# CAN.net
KiCad netlist of a schematic drawn in Altium Designer
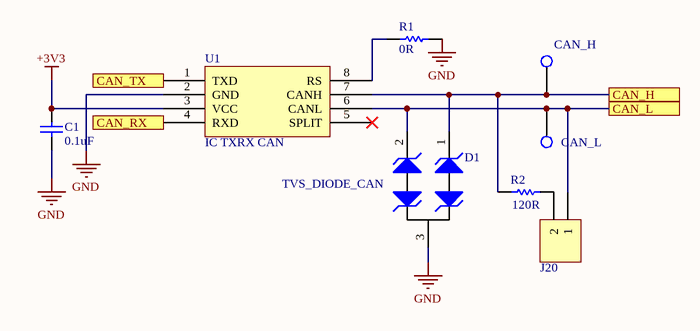
[diagram p0: CAN.SchDoc]

(export (version "E")
  (design (tool "Eeschema 10.0.6"))
  (components
    (comp (ref "C1")
      (value "0.1uF")
      (footprint "CAPC0603(1608)55_N")
      (description "CAP CER 0.1UF 16V X7R 0603")
      (fields (field (name "MANUFACTURER") "Yageo") (field (name "MPN") "CC0603KRX7R7BB104"))
      (libsource (lib "UWRT_Schematic_Library_2019") (part "CAP_0.1uF_16V_0603"))
    )
    (comp (ref "D1")
      (value "TVS_DIODE_CAN")
      (footprint "UWRT_Footprint_Library_2019:TVS_DIODE_CAN")
      (description "TVS DIODE 24V 41V SOT323-3")
      (fields (field (name "MANUFACTURER") "Nexperia USA Inc.") (field (name "MPN") "PESD2CAN,215"))
      (libsource (lib "UWRT_Schematic_Library_2019") (part "TVS_DIODE_CAN"))
    )
    (comp (ref "J20")
      (value "JUMPER_2")
      (footprint "HDR1X2")
      (description "HEADER 2X1")
      (libsource (lib "UWRT_Schematic_Library_2019") (part "JUMPER_2"))
    )
    (comp (ref "R1")
      (value "0R")
      (footprint "RESC0603(1608)_N")
      (description "RES SMD 0 OHM JUMPER 1/10W 0603")
      (fields (field (name "MANUFACTURER") "Yageo") (field (name "MPN") "RC0603JR-070RL"))
      (libsource (lib "UWRT_Schematic_Library_2019") (part "RES_0R_0603"))
    )
    (comp (ref "R2")
      (value "120R")
      (footprint "RESC0603(1608)_N")
      (description "RES SMD 120 OHM 5% 1/10W 0603")
      (fields (field (name "MANUFACTURER") "Yageo") (field (name "TOLERANCE") "5%"))
      (libsource (lib "UWRT_Schematic_Library_2019") (part "RES_120R_0603"))
    )
    (comp (ref "TP1")
      (value "CAN_H")
      (footprint "TESTPOINT_LOOP")
      (description "PC TEST POINT MINIATURE WHITE")
      (fields
        (field (name "DIGIKEY PART NUMBER") "36-5002-ND")
        (field (name "MANUFACTURER") "Keystone Electronics")
      )
      (libsource (lib "UWRT_Schematic_Library_2019") (part "TESTPOINT_LOOP"))
    )
    (comp (ref "TP2")
      (value "CAN_L")
      (footprint "TESTPOINT_LOOP")
      (description "PC TEST POINT MINIATURE WHITE")
      (fields
        (field (name "DIGIKEY PART NUMBER") "36-5002-ND")
        (field (name "MANUFACTURER") "Keystone Electronics")
      )
      (libsource (lib "UWRT_Schematic_Library_2019") (part "TESTPOINT_LOOP"))
    )
    (comp (ref "U1")
      (value "IC TXRX CAN")
      (footprint "LT-S8_N")
      (description "IC TXRX CAN 4MBPS 8SO")
      (fields (field (name "MANUFACTURER") "Linear Technologies") (field (name "MPN") "LTC2875IS8#PBF"))
      (libsource (lib "UWRT_Schematic_Library_2019") (part "LTC2875"))
    )
  )
  (nets
    (net (code "1") (name "+3V3") (class "Default")
      (node (ref "C1") (pin "2") (pinfunction "2_2") (pintype "passive"))
      (node (ref "U1") (pin "3") (pinfunction "VCC_3") (pintype "passive"))
    )
    (net (code "2") (name "/CAN_H") (class "Default")
      (node (ref "D1") (pin "1") (pinfunction "1_1") (pintype "passive"))
      (node (ref "R2") (pin "1") (pinfunction "1_1") (pintype "passive"))
      (node (ref "TP1") (pin "1") (pintype "passive"))
      (node (ref "U1") (pin "7") (pinfunction "CANH_7") (pintype "passive"))
    )
    (net (code "3") (name "/CAN_L") (class "Default")
      (node (ref "D1") (pin "2") (pinfunction "2_2") (pintype "passive"))
      (node (ref "J20") (pin "1") (pinfunction "1_1") (pintype "passive"))
      (node (ref "TP2") (pin "1") (pintype "passive"))
      (node (ref "U1") (pin "6") (pinfunction "CANL_6") (pintype "passive"))
    )
    (net (code "4") (name "/CAN_RX") (class "Default")
      (node (ref "U1") (pin "4") (pinfunction "RXD_4") (pintype "passive"))
    )
    (net (code "5") (name "/CAN_TX") (class "Default")
      (node (ref "U1") (pin "1") (pinfunction "TXD_1") (pintype "passive"))
    )
    (net (code "6") (name "GND") (class "Default")
      (node (ref "C1") (pin "1") (pinfunction "1_1") (pintype "passive"))
      (node (ref "D1") (pin "3") (pinfunction "3_3") (pintype "passive"))
      (node (ref "R1") (pin "2") (pinfunction "2_2") (pintype "passive"))
      (node (ref "U1") (pin "2") (pinfunction "GND_2") (pintype "passive"))
    )
    (net (code "7") (name "Net-(J20-Pad2)") (class "Default")
      (node (ref "J20") (pin "2") (pinfunction "2_2") (pintype "passive"))
      (node (ref "R2") (pin "2") (pinfunction "2_2") (pintype "passive"))
    )
    (net (code "8") (name "Net-(U1-RS)") (class "Default")
      (node (ref "R1") (pin "1") (pinfunction "1_1") (pintype "passive"))
      (node (ref "U1") (pin "8") (pinfunction "RS_8") (pintype "passive"))
    )
    (net (code "9") (name "unconnected-(U1-SPLIT-Pad5)") (class "Default")
      (node (ref "U1") (pin "5") (pinfunction "SPLIT_5") (pintype "passive+no_connect"))
    )
  )
)
